# WiFiSensor.net
KiCad netlist of a schematic drawn in EAGLE
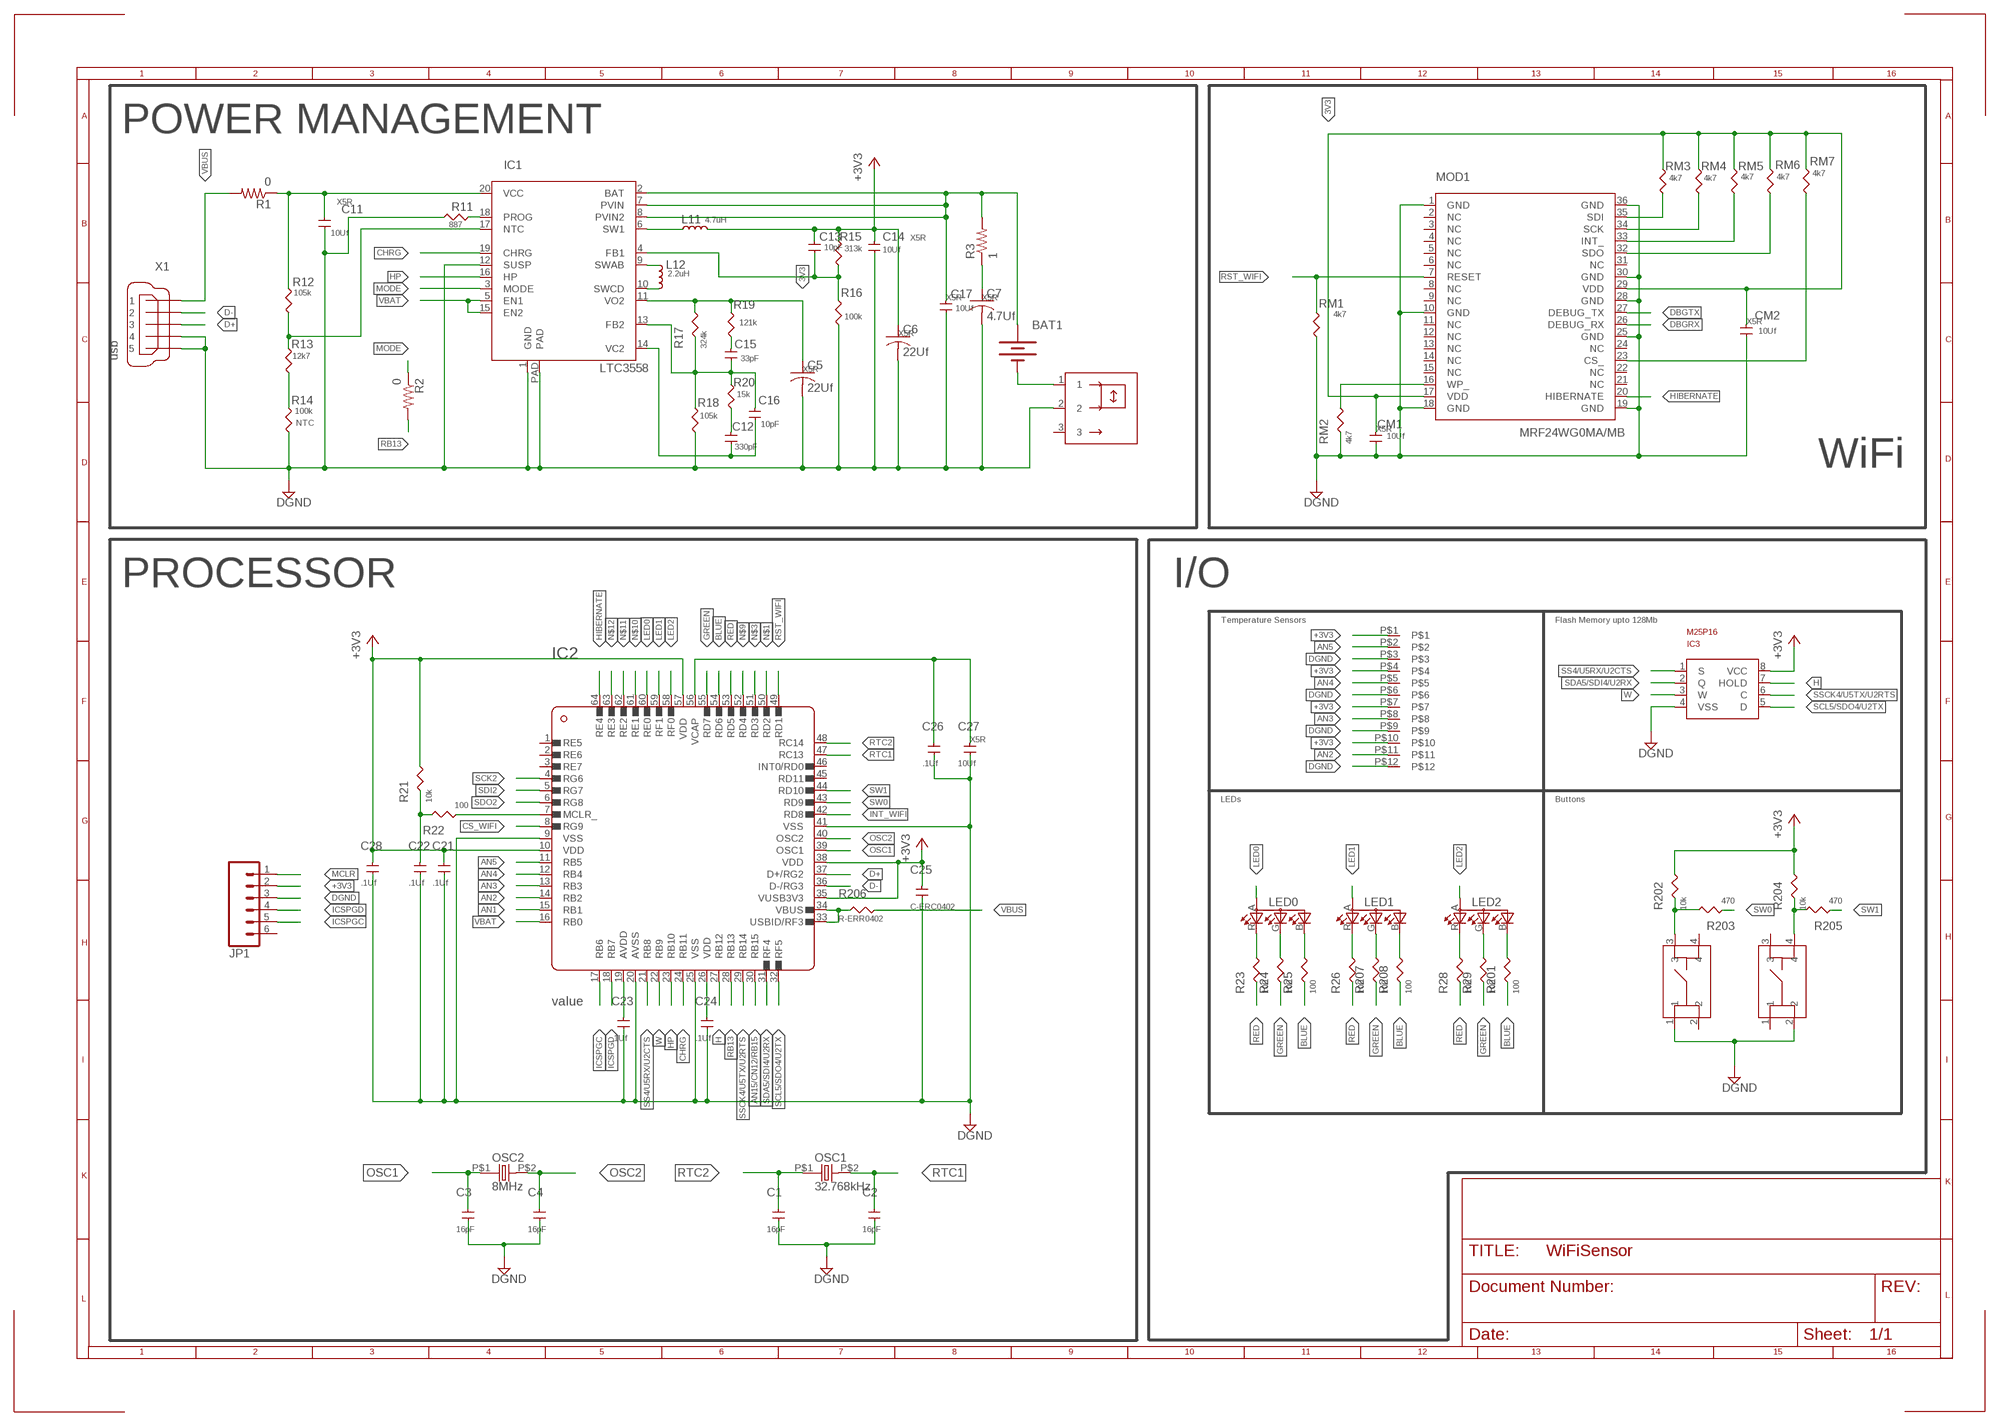
[diagram p0: schematic, sheet 1]

(export (version "E")
  (design (tool "Eeschema 10.0.6"))
  (components
    (comp (ref "BAT1")
      (value "BATTERY245PTH")
      (footprint "eagle-import:BATTCON_245MM_PTH")
      (libsource (lib "eagle-import") (part "BATTERY245PTH"))
    )
    (comp (ref "C1")
      (value "16pF")
      (footprint "eagle-import:C0402")
      (libsource (lib "eagle-import") (part "C-ERC0402"))
    )
    (comp (ref "C2")
      (value "16pF")
      (footprint "eagle-import:C0402")
      (libsource (lib "eagle-import") (part "C-ERC0402"))
    )
    (comp (ref "C3")
      (value "16pF")
      (footprint "eagle-import:C0402")
      (libsource (lib "eagle-import") (part "C-ERC0402"))
    )
    (comp (ref "C4")
      (value "16pF")
      (footprint "eagle-import:C0402")
      (libsource (lib "eagle-import") (part "C-ERC0402"))
    )
    (comp (ref "C5")
      (value "22Uf")
      (footprint "eagle-import:C0805")
      (fields (field (name "TEMPCHAR") "X5R"))
      (libsource (lib "eagle-import") (part "C-USC0805"))
    )
    (comp (ref "C6")
      (value "22Uf")
      (footprint "eagle-import:C0805")
      (fields (field (name "TEMPCHAR") "X5R"))
      (libsource (lib "eagle-import") (part "C-USC0805"))
    )
    (comp (ref "C7")
      (value "4.7Uf")
      (footprint "eagle-import:C0402")
      (fields (field (name "TEMPCHAR") "X5R"))
      (libsource (lib "eagle-import") (part "C-USC0402"))
    )
    (comp (ref "C11")
      (value "10Uf")
      (footprint "eagle-import:C0805")
      (fields (field (name "TEMPCHAR") "X5R"))
      (libsource (lib "eagle-import") (part "C-ER"))
    )
    (comp (ref "C12")
      (value "330pF")
      (footprint "eagle-import:C0402")
      (libsource (lib "eagle-import") (part "C-ERC0402"))
    )
    (comp (ref "C13")
      (value "10pF")
      (footprint "eagle-import:C0402")
      (libsource (lib "eagle-import") (part "C-ERC0402"))
    )
    (comp (ref "C14")
      (value "10Uf")
      (footprint "eagle-import:C0805")
      (fields (field (name "TEMPCHAR") "X5R"))
      (libsource (lib "eagle-import") (part "C-ER"))
    )
    (comp (ref "C15")
      (value "33pF")
      (footprint "eagle-import:C0402")
      (libsource (lib "eagle-import") (part "C-ERC0402"))
    )
    (comp (ref "C16")
      (value "10pF")
      (footprint "eagle-import:C0402")
      (libsource (lib "eagle-import") (part "C-ERC0402"))
    )
    (comp (ref "C17")
      (value "10Uf")
      (footprint "eagle-import:C0805")
      (fields (field (name "TEMPCHAR") "X5R"))
      (libsource (lib "eagle-import") (part "C-ER"))
    )
    (comp (ref "C21")
      (value ".1Uf")
      (footprint "eagle-import:C0402")
      (libsource (lib "eagle-import") (part "C-ERC0402"))
    )
    (comp (ref "C22")
      (value ".1Uf")
      (footprint "eagle-import:C0402")
      (libsource (lib "eagle-import") (part "C-ERC0402"))
    )
    (comp (ref "C23")
      (value ".1Uf")
      (footprint "eagle-import:C0402")
      (libsource (lib "eagle-import") (part "C-ERC0402"))
    )
    (comp (ref "C24")
      (value ".1Uf")
      (footprint "eagle-import:C0402")
      (libsource (lib "eagle-import") (part "C-ERC0402"))
    )
    (comp (ref "C25")
      (value "C-ERC0402")
      (footprint "eagle-import:C0402")
      (libsource (lib "eagle-import") (part "C-ERC0402"))
    )
    (comp (ref "C26")
      (value ".1Uf")
      (footprint "eagle-import:C0402")
      (libsource (lib "eagle-import") (part "C-ERC0402"))
    )
    (comp (ref "C27")
      (value "10Uf")
      (footprint "eagle-import:C0805")
      (fields (field (name "TEMPCHAR") "X5R"))
      (libsource (lib "eagle-import") (part "C-ER"))
    )
    (comp (ref "C28")
      (value ".1Uf")
      (footprint "eagle-import:C0402")
      (libsource (lib "eagle-import") (part "C-ERC0402"))
    )
    (comp (ref "CM1")
      (value "10Uf")
      (footprint "eagle-import:C0805")
      (fields (field (name "TEMPCHAR") "X5R"))
      (libsource (lib "eagle-import") (part "C-ER"))
    )
    (comp (ref "CM2")
      (value "10Uf")
      (footprint "eagle-import:C0805")
      (fields (field (name "TEMPCHAR") "X5R"))
      (libsource (lib "eagle-import") (part "C-ER"))
    )
    (comp (ref "IC1")
      (value "LTC3558")
      (footprint "eagle-import:QFN20")
      (libsource (lib "eagle-import") (part "LTC3558"))
    )
    (comp (ref "IC2")
      (value "PICMX32695F512H")
      (footprint "eagle-import:TQFP64")
      (libsource (lib "eagle-import") (part "PICMX32695F512H"))
    )
    (comp (ref "IC3")
      (value "M25P16")
      (footprint "eagle-import:VDFPN8")
      (libsource (lib "eagle-import") (part "M25P16"))
    )
    (comp (ref "JP1")
      (value "M06LOCK")
      (footprint "eagle-import:1X06_LOCK")
      (libsource (lib "eagle-import") (part "M06LOCK"))
    )
    (comp (ref "L11")
      (value "4.7uH")
      (footprint "eagle-import:L3010")
      (libsource (lib "eagle-import") (part "L-ER"))
    )
    (comp (ref "L12")
      (value "2.2uH")
      (footprint "eagle-import:L3010")
      (libsource (lib "eagle-import") (part "L-ER"))
    )
    (comp (ref "LED0")
      (value "1X1RGB")
      (footprint "eagle-import:1X1")
      (libsource (lib "eagle-import") (part "1X1RGB"))
    )
    (comp (ref "LED1")
      (value "1X1RGB")
      (footprint "eagle-import:1X1")
      (libsource (lib "eagle-import") (part "1X1RGB"))
    )
    (comp (ref "LED2")
      (value "1X1RGB")
      (footprint "eagle-import:1X1")
      (libsource (lib "eagle-import") (part "1X1RGB"))
    )
    (comp (ref "MOD1")
      (value "MRF24WG0MA/MB")
      (footprint "eagle-import:MRF24")
      (libsource (lib "eagle-import") (part "MRF24WG0MA/MB"))
    )
    (comp (ref "OSC1")
      (value "32.768kHz")
      (footprint "eagle-import:ECX39")
      (fields (field (name "DIGIPART") "XC1658CT-ND"))
      (libsource (lib "eagle-import") (part "ECX32"))
    )
    (comp (ref "OSC2")
      (value "8MHz")
      (footprint "eagle-import:CX532")
      (fields (field (name "DIGIPART") "XC1658CT-ND"))
      (libsource (lib "eagle-import") (part "CX532"))
    )
    (comp (ref "R1")
      (value "0")
      (footprint "eagle-import:R1206")
      (libsource (lib "eagle-import") (part "R-US_R1206"))
    )
    (comp (ref "R2")
      (value "0")
      (footprint "eagle-import:R1206")
      (libsource (lib "eagle-import") (part "R-US_R1206"))
    )
    (comp (ref "R3")
      (value "1")
      (footprint "eagle-import:R0402")
      (libsource (lib "eagle-import") (part "R-US_R0402"))
    )
    (comp (ref "R11")
      (value "887")
      (footprint "eagle-import:R0402")
      (libsource (lib "eagle-import") (part "R-ERR0402"))
    )
    (comp (ref "R12")
      (value "105k")
      (footprint "eagle-import:R0402")
      (libsource (lib "eagle-import") (part "R-ERR0402"))
    )
    (comp (ref "R13")
      (value "12k7")
      (footprint "eagle-import:R0402")
      (libsource (lib "eagle-import") (part "R-ERR0402"))
    )
    (comp (ref "R14")
      (value "100k")
      (footprint "eagle-import:R0402")
      (fields (field (name "NTC") "NTC"))
      (libsource (lib "eagle-import") (part "R-ERR0402"))
    )
    (comp (ref "R15")
      (value "313k")
      (footprint "eagle-import:R0402")
      (libsource (lib "eagle-import") (part "R-ERR0402"))
    )
    (comp (ref "R16")
      (value "100k")
      (footprint "eagle-import:R0402")
      (libsource (lib "eagle-import") (part "R-ERR0402"))
    )
    (comp (ref "R17")
      (value "324k")
      (footprint "eagle-import:R0402")
      (libsource (lib "eagle-import") (part "R-ERR0402"))
    )
    (comp (ref "R18")
      (value "105k")
      (footprint "eagle-import:R0402")
      (libsource (lib "eagle-import") (part "R-ERR0402"))
    )
    (comp (ref "R19")
      (value "121k")
      (footprint "eagle-import:R0402")
      (libsource (lib "eagle-import") (part "R-ERR0402"))
    )
    (comp (ref "R20")
      (value "15k")
      (footprint "eagle-import:R0402")
      (libsource (lib "eagle-import") (part "R-ERR0402"))
    )
    (comp (ref "R21")
      (value "10k")
      (footprint "eagle-import:R0402")
      (libsource (lib "eagle-import") (part "R-ERR0402"))
    )
    (comp (ref "R22")
      (value "100")
      (footprint "eagle-import:R0402")
      (libsource (lib "eagle-import") (part "R-ERR0402"))
    )
    (comp (ref "R23")
      (value "100")
      (footprint "eagle-import:R0402")
      (libsource (lib "eagle-import") (part "R-ERR0402"))
    )
    (comp (ref "R24")
      (value "100")
      (footprint "eagle-import:R0402")
      (libsource (lib "eagle-import") (part "R-ERR0402"))
    )
    (comp (ref "R25")
      (value "100")
      (footprint "eagle-import:R0402")
      (libsource (lib "eagle-import") (part "R-ERR0402"))
    )
    (comp (ref "R26")
      (value "100")
      (footprint "eagle-import:R0402")
      (libsource (lib "eagle-import") (part "R-ERR0402"))
    )
    (comp (ref "R28")
      (value "100")
      (footprint "eagle-import:R0402")
      (libsource (lib "eagle-import") (part "R-ERR0402"))
    )
    (comp (ref "R29")
      (value "100")
      (footprint "eagle-import:R0402")
      (libsource (lib "eagle-import") (part "R-ERR0402"))
    )
    (comp (ref "R201")
      (value "100")
      (footprint "eagle-import:R0402")
      (libsource (lib "eagle-import") (part "R-ERR0402"))
    )
    (comp (ref "R202")
      (value "10k")
      (footprint "eagle-import:R0402")
      (libsource (lib "eagle-import") (part "R-ERR0402"))
    )
    (comp (ref "R203")
      (value "470")
      (footprint "eagle-import:R0402")
      (libsource (lib "eagle-import") (part "R-ERR0402"))
    )
    (comp (ref "R204")
      (value "10k")
      (footprint "eagle-import:R0402")
      (libsource (lib "eagle-import") (part "R-ERR0402"))
    )
    (comp (ref "R205")
      (value "470")
      (footprint "eagle-import:R0402")
      (libsource (lib "eagle-import") (part "R-ERR0402"))
    )
    (comp (ref "R206")
      (value "R-ERR0402")
      (footprint "eagle-import:R0402")
      (libsource (lib "eagle-import") (part "R-ERR0402"))
    )
    (comp (ref "R207")
      (value "100")
      (footprint "eagle-import:R0402")
      (libsource (lib "eagle-import") (part "R-ERR0402"))
    )
    (comp (ref "R208")
      (value "100")
      (footprint "eagle-import:R0402")
      (libsource (lib "eagle-import") (part "R-ERR0402"))
    )
    (comp (ref "RM1")
      (value "4k7")
      (footprint "eagle-import:R0402")
      (libsource (lib "eagle-import") (part "R-ERR0402"))
    )
    (comp (ref "RM2")
      (value "4k7")
      (footprint "eagle-import:R0402")
      (libsource (lib "eagle-import") (part "R-ERR0402"))
    )
    (comp (ref "RM3")
      (value "4k7")
      (footprint "eagle-import:R0402")
      (libsource (lib "eagle-import") (part "R-ERR0402"))
    )
    (comp (ref "RM4")
      (value "4k7")
      (footprint "eagle-import:R0402")
      (libsource (lib "eagle-import") (part "R-ERR0402"))
    )
    (comp (ref "RM5")
      (value "4k7")
      (footprint "eagle-import:R0402")
      (libsource (lib "eagle-import") (part "R-ERR0402"))
    )
    (comp (ref "RM6")
      (value "4k7")
      (footprint "eagle-import:R0402")
      (libsource (lib "eagle-import") (part "R-ERR0402"))
    )
    (comp (ref "RM7")
      (value "4k7")
      (footprint "eagle-import:R0402")
      (libsource (lib "eagle-import") (part "R-ERR0402"))
    )
    (comp (ref "SENSORS")
      (value "12_127")
      (footprint "eagle-import:12-127")
      (libsource (lib "eagle-import") (part "12_127"))
    )
    (comp (ref "U$1")
      (value "C&K_JS")
      (footprint "eagle-import:SAQN")
      (libsource (lib "eagle-import") (part "C&K_JS"))
    )
    (comp (ref "U$2")
      (value "ADTS")
      (footprint "eagle-import:4X5")
      (libsource (lib "eagle-import") (part "ADTS"))
    )
    (comp (ref "U$3")
      (value "ADTS")
      (footprint "eagle-import:4X5")
      (libsource (lib "eagle-import") (part "ADTS"))
    )
    (comp (ref "X1")
      (value "usb")
      (footprint "eagle-import:UX60A-MB-5ST")
      (libsource (lib "eagle-import") (part "MINI-USB-UX60A-MB-5ST"))
    )
  )
  (nets
    (net (code "1") (name "+3V3") (class "Default")
      (node (ref "C13") (pin "2") (pinfunction "P$2_2") (pintype "bidirectional"))
      (node (ref "C14") (pin "2") (pinfunction "P$2_2") (pintype "bidirectional"))
      (node (ref "C21") (pin "2") (pinfunction "P$2_2") (pintype "bidirectional"))
      (node (ref "C23") (pin "2") (pinfunction "P$2_2") (pintype "bidirectional"))
      (node (ref "C24") (pin "2") (pinfunction "P$2_2") (pintype "bidirectional"))
      (node (ref "C25") (pin "2") (pinfunction "P$2_2") (pintype "bidirectional"))
      (node (ref "C28") (pin "2") (pinfunction "P$2_2") (pintype "bidirectional"))
      (node (ref "C6") (pin "1") (pinfunction "1_1") (pintype "passive"))
      (node (ref "IC2") (pin "10") (pinfunction "VDD_10") (pintype "bidirectional"))
      (node (ref "IC2") (pin "19") (pinfunction "AVDD_19") (pintype "bidirectional"))
      (node (ref "IC2") (pin "26") (pinfunction "VDD_26") (pintype "bidirectional"))
      (node (ref "IC2") (pin "35") (pinfunction "VUSB3V3_35") (pintype "bidirectional"))
      (node (ref "IC2") (pin "38") (pinfunction "VDD_38") (pintype "bidirectional"))
      (node (ref "IC2") (pin "57") (pinfunction "VDD_57") (pintype "bidirectional"))
      (node (ref "IC3") (pin "8") (pinfunction "VCC_8") (pintype "bidirectional"))
      (node (ref "JP1") (pin "2") (pinfunction "2_2") (pintype "passive"))
      (node (ref "L11") (pin "P$2") (pinfunction "P$2_P$2") (pintype "bidirectional"))
      (node (ref "R15") (pin "2") (pinfunction "P$2_2") (pintype "bidirectional"))
      (node (ref "R202") (pin "2") (pinfunction "P$2_2") (pintype "bidirectional"))
      (node (ref "R204") (pin "2") (pinfunction "P$2_2") (pintype "bidirectional"))
      (node (ref "R21") (pin "2") (pinfunction "P$2_2") (pintype "bidirectional"))
      (node (ref "SENSORS") (pin "P$1") (pinfunction "P$1_P$1") (pintype "bidirectional"))
      (node (ref "SENSORS") (pin "P$10") (pinfunction "P$10_P$10") (pintype "bidirectional"))
      (node (ref "SENSORS") (pin "P$4") (pinfunction "P$4_P$4") (pintype "bidirectional"))
      (node (ref "SENSORS") (pin "P$7") (pinfunction "P$7_P$7") (pintype "bidirectional"))
    )
    (net (code "2") (name "3V3") (class "Default")
      (node (ref "C5") (pin "1") (pinfunction "1_1") (pintype "passive"))
      (node (ref "CM1") (pin "2") (pinfunction "P$2_2") (pintype "bidirectional"))
      (node (ref "CM2") (pin "2") (pinfunction "P$2_2") (pintype "bidirectional"))
      (node (ref "IC1") (pin "11") (pinfunction "VO2_11") (pintype "bidirectional"))
      (node (ref "MOD1") (pin "17") (pinfunction "VDD_17") (pintype "bidirectional"))
      (node (ref "MOD1") (pin "29") (pinfunction "VDD_29") (pintype "bidirectional"))
      (node (ref "R17") (pin "2") (pinfunction "P$2_2") (pintype "bidirectional"))
      (node (ref "R19") (pin "2") (pinfunction "P$2_2") (pintype "bidirectional"))
      (node (ref "RM3") (pin "2") (pinfunction "P$2_2") (pintype "bidirectional"))
      (node (ref "RM4") (pin "2") (pinfunction "P$2_2") (pintype "bidirectional"))
      (node (ref "RM5") (pin "2") (pinfunction "P$2_2") (pintype "bidirectional"))
      (node (ref "RM6") (pin "2") (pinfunction "P$2_2") (pintype "bidirectional"))
      (node (ref "RM7") (pin "2") (pinfunction "P$2_2") (pintype "bidirectional"))
    )
    (net (code "3") (name "AN1") (class "Default")
      (node (ref "IC2") (pin "15") (pinfunction "RB1_15") (pintype "bidirectional"))
    )
    (net (code "4") (name "AN2") (class "Default")
      (node (ref "IC2") (pin "14") (pinfunction "RB2_14") (pintype "bidirectional"))
      (node (ref "SENSORS") (pin "P$11") (pinfunction "P$11_P$11") (pintype "bidirectional"))
    )
    (net (code "5") (name "AN3") (class "Default")
      (node (ref "IC2") (pin "13") (pinfunction "RB3_13") (pintype "bidirectional"))
      (node (ref "SENSORS") (pin "P$8") (pinfunction "P$8_P$8") (pintype "bidirectional"))
    )
    (net (code "6") (name "AN4") (class "Default")
      (node (ref "IC2") (pin "12") (pinfunction "RB4_12") (pintype "bidirectional"))
      (node (ref "SENSORS") (pin "P$5") (pinfunction "P$5_P$5") (pintype "bidirectional"))
    )
    (net (code "7") (name "AN5") (class "Default")
      (node (ref "IC2") (pin "11") (pinfunction "RB5_11") (pintype "bidirectional"))
      (node (ref "SENSORS") (pin "P$2") (pinfunction "P$2_P$2") (pintype "bidirectional"))
    )
    (net (code "8") (name "AN15{slash}CN12{slash}RB15") (class "Default")
      (node (ref "IC2") (pin "30") (pinfunction "RB15_30") (pintype "bidirectional"))
    )
    (net (code "9") (name "BLUE") (class "Default")
      (node (ref "IC2") (pin "54") (pinfunction "RD6_54") (pintype "bidirectional"))
      (node (ref "R201") (pin "1") (pinfunction "P$1_1") (pintype "bidirectional"))
      (node (ref "R208") (pin "1") (pinfunction "P$1_1") (pintype "bidirectional"))
      (node (ref "R25") (pin "1") (pinfunction "P$1_1") (pintype "bidirectional"))
    )
    (net (code "10") (name "CHRG") (class "Default")
      (node (ref "IC1") (pin "19") (pinfunction "CHRG_19") (pintype "bidirectional"))
      (node (ref "IC2") (pin "24") (pinfunction "RB11_24") (pintype "bidirectional"))
    )
    (net (code "11") (name "CS_WIFI") (class "Default")
      (node (ref "IC2") (pin "8") (pinfunction "RG9_8") (pintype "bidirectional"))
      (node (ref "MOD1") (pin "23") (pinfunction "CS__23") (pintype "bidirectional"))
      (node (ref "RM7") (pin "1") (pinfunction "P$1_1") (pintype "bidirectional"))
    )
    (net (code "12") (name "D+") (class "Default")
      (node (ref "IC2") (pin "37") (pinfunction "D+/RG2_37") (pintype "bidirectional"))
      (node (ref "X1") (pin "3") (pinfunction "3_3") (pintype "input"))
    )
    (net (code "13") (name "D-") (class "Default")
      (node (ref "IC2") (pin "36") (pinfunction "D-/RG3_36") (pintype "bidirectional"))
      (node (ref "X1") (pin "2") (pinfunction "2_2") (pintype "input"))
    )
    (net (code "14") (name "DBGRX") (class "Default")
      (node (ref "MOD1") (pin "26") (pinfunction "DEBUG_RX_26") (pintype "bidirectional"))
    )
    (net (code "15") (name "DBGTX") (class "Default")
      (node (ref "MOD1") (pin "27") (pinfunction "DEBUG_TX_27") (pintype "bidirectional"))
    )
    (net (code "16") (name "DGND") (class "Default")
      (node (ref "C1") (pin "1") (pinfunction "P$1_1") (pintype "bidirectional"))
      (node (ref "C11") (pin "1") (pinfunction "P$1_1") (pintype "bidirectional"))
      (node (ref "C14") (pin "1") (pinfunction "P$1_1") (pintype "bidirectional"))
      (node (ref "C17") (pin "1") (pinfunction "P$1_1") (pintype "bidirectional"))
      (node (ref "C2") (pin "1") (pinfunction "P$1_1") (pintype "bidirectional"))
      (node (ref "C21") (pin "1") (pinfunction "P$1_1") (pintype "bidirectional"))
      (node (ref "C22") (pin "1") (pinfunction "P$1_1") (pintype "bidirectional"))
      (node (ref "C23") (pin "1") (pinfunction "P$1_1") (pintype "bidirectional"))
      (node (ref "C24") (pin "1") (pinfunction "P$1_1") (pintype "bidirectional"))
      (node (ref "C25") (pin "1") (pinfunction "P$1_1") (pintype "bidirectional"))
      (node (ref "C26") (pin "1") (pinfunction "P$1_1") (pintype "bidirectional"))
      (node (ref "C27") (pin "1") (pinfunction "P$1_1") (pintype "bidirectional"))
      (node (ref "C28") (pin "1") (pinfunction "P$1_1") (pintype "bidirectional"))
      (node (ref "C3") (pin "1") (pinfunction "P$1_1") (pintype "bidirectional"))
      (node (ref "C4") (pin "1") (pinfunction "P$1_1") (pintype "bidirectional"))
      (node (ref "C5") (pin "2") (pinfunction "2_2") (pintype "passive"))
      (node (ref "C6") (pin "2") (pinfunction "2_2") (pintype "passive"))
      (node (ref "C7") (pin "2") (pinfunction "2_2") (pintype "passive"))
      (node (ref "CM1") (pin "1") (pinfunction "P$1_1") (pintype "bidirectional"))
      (node (ref "CM2") (pin "1") (pinfunction "P$1_1") (pintype "bidirectional"))
      (node (ref "IC1") (pin "1") (pinfunction "GND_1") (pintype "bidirectional"))
      (node (ref "IC1") (pin "12") (pinfunction "SUSP_12") (pintype "bidirectional"))
      (node (ref "IC1") (pin "PAD") (pinfunction "PAD_PAD") (pintype "bidirectional"))
      (node (ref "IC2") (pin "20") (pinfunction "AVSS_20") (pintype "bidirectional"))
      (node (ref "IC2") (pin "25") (pinfunction "VSS_25") (pintype "bidirectional"))
      (node (ref "IC2") (pin "41") (pinfunction "VSS_41") (pintype "bidirectional"))
      (node (ref "IC2") (pin "9") (pinfunction "VSS_9") (pintype "bidirectional"))
      (node (ref "IC3") (pin "4") (pinfunction "VSS_4") (pintype "bidirectional"))
      (node (ref "JP1") (pin "3") (pinfunction "3_3") (pintype "passive"))
      (node (ref "MOD1") (pin "1") (pinfunction "GND_1") (pintype "bidirectional"))
      (node (ref "MOD1") (pin "10") (pinfunction "GND_10") (pintype "bidirectional"))
      (node (ref "MOD1") (pin "18") (pinfunction "GND_18") (pintype "bidirectional"))
      (node (ref "MOD1") (pin "19") (pinfunction "GND_19") (pintype "bidirectional"))
      (node (ref "MOD1") (pin "25") (pinfunction "GND_25") (pintype "bidirectional"))
      (node (ref "MOD1") (pin "28") (pinfunction "GND_28") (pintype "bidirectional"))
      (node (ref "MOD1") (pin "30") (pinfunction "GND_30") (pintype "bidirectional"))
      (node (ref "MOD1") (pin "36") (pinfunction "GND_36") (pintype "bidirectional"))
      (node (ref "R11") (pin "2") (pinfunction "P$2_2") (pintype "bidirectional"))
      (node (ref "R14") (pin "1") (pinfunction "P$1_1") (pintype "bidirectional"))
      (node (ref "R16") (pin "1") (pinfunction "P$1_1") (pintype "bidirectional"))
      (node (ref "R18") (pin "1") (pinfunction "P$1_1") (pintype "bidirectional"))
      (node (ref "RM1") (pin "1") (pinfunction "P$1_1") (pintype "bidirectional"))
      (node (ref "RM2") (pin "1") (pinfunction "P$1_1") (pintype "bidirectional"))
      (node (ref "SENSORS") (pin "P$12") (pinfunction "P$12_P$12") (pintype "bidirectional"))
      (node (ref "SENSORS") (pin "P$3") (pinfunction "P$3_P$3") (pintype "bidirectional"))
      (node (ref "SENSORS") (pin "P$6") (pinfunction "P$6_P$6") (pintype "bidirectional"))
      (node (ref "SENSORS") (pin "P$9") (pinfunction "P$9_P$9") (pintype "bidirectional"))
      (node (ref "U$1") (pin "2") (pinfunction "2_2") (pintype "bidirectional"))
      (node (ref "U$2") (pin "2") (pinfunction "2_2") (pintype "bidirectional"))
      (node (ref "U$3") (pin "1") (pinfunction "1_1") (pintype "bidirectional"))
      (node (ref "X1") (pin "4") (pinfunction "4_4") (pintype "input"))
      (node (ref "X1") (pin "5") (pinfunction "5_5") (pintype "input"))
    )
    (net (code "17") (name "GREEN") (class "Default")
      (node (ref "IC2") (pin "55") (pinfunction "RD7_55") (pintype "bidirectional"))
      (node (ref "R207") (pin "1") (pinfunction "P$1_1") (pintype "bidirectional"))
      (node (ref "R24") (pin "1") (pinfunction "P$1_1") (pintype "bidirectional"))
      (node (ref "R29") (pin "1") (pinfunction "P$1_1") (pintype "bidirectional"))
    )
    (net (code "18") (name "H") (class "Default")
      (node (ref "IC2") (pin "27") (pinfunction "RB12_27") (pintype "bidirectional"))
      (node (ref "IC3") (pin "7") (pinfunction "HOLD_7") (pintype "bidirectional"))
    )
    (net (code "19") (name "HIBERNATE") (class "Default")
      (node (ref "IC2") (pin "64") (pinfunction "RE4_64") (pintype "bidirectional"))
      (node (ref "MOD1") (pin "20") (pinfunction "HIBERNATE_20") (pintype "bidirectional"))
    )
    (net (code "20") (name "HP") (class "Default")
      (node (ref "IC1") (pin "16") (pinfunction "HP_16") (pintype "bidirectional"))
      (node (ref "IC2") (pin "23") (pinfunction "RB10_23") (pintype "bidirectional"))
    )
    (net (code "21") (name "ICSPGC") (class "Default")
      (node (ref "IC2") (pin "17") (pinfunction "RB6_17") (pintype "bidirectional"))
      (node (ref "JP1") (pin "5") (pinfunction "5_5") (pintype "passive"))
    )
    (net (code "22") (name "ICSPGD") (class "Default")
      (node (ref "IC2") (pin "18") (pinfunction "RB7_18") (pintype "bidirectional"))
      (node (ref "JP1") (pin "4") (pinfunction "4_4") (pintype "passive"))
    )
    (net (code "23") (name "INT_WIFI") (class "Default")
      (node (ref "IC2") (pin "42") (pinfunction "RD8_42") (pintype "bidirectional"))
      (node (ref "MOD1") (pin "33") (pinfunction "INT__33") (pintype "bidirectional"))
      (node (ref "RM5") (pin "1") (pinfunction "P$1_1") (pintype "bidirectional"))
    )
    (net (code "24") (name "LED0") (class "Default")
      (node (ref "IC2") (pin "60") (pinfunction "RE0_60") (pintype "bidirectional"))
      (node (ref "LED0") (pin "A") (pinfunction "A2_A") (pintype "passive"))
    )
    (net (code "25") (name "LED1") (class "Default")
      (node (ref "IC2") (pin "59") (pinfunction "RF1_59") (pintype "bidirectional"))
      (node (ref "LED1") (pin "A") (pinfunction "A2_A") (pintype "passive"))
    )
    (net (code "26") (name "LED2") (class "Default")
      (node (ref "IC2") (pin "58") (pinfunction "RF0_58") (pintype "bidirectional"))
      (node (ref "LED2") (pin "A") (pinfunction "A2_A") (pintype "passive"))
    )
    (net (code "27") (name "MCLR") (class "Default")
      (node (ref "C22") (pin "2") (pinfunction "P$2_2") (pintype "bidirectional"))
      (node (ref "JP1") (pin "1") (pinfunction "1_1") (pintype "passive"))
      (node (ref "R21") (pin "1") (pinfunction "P$1_1") (pintype "bidirectional"))
      (node (ref "R22") (pin "2") (pinfunction "P$2_2") (pintype "bidirectional"))
    )
    (net (code "28") (name "MODE") (class "Default")
      (node (ref "IC1") (pin "3") (pinfunction "MODE_3") (pintype "bidirectional"))
      (node (ref "R2") (pin "1") (pinfunction "1_1") (pintype "passive"))
    )
    (net (code "29") (name "N$1") (class "Default")
      (node (ref "IC2") (pin "50") (pinfunction "RD2_50") (pintype "bidirectional"))
    )
    (net (code "30") (name "N$3") (class "Default")
      (node (ref "IC2") (pin "51") (pinfunction "RD3_51") (pintype "bidirectional"))
    )
    (net (code "31") (name "N$9") (class "Default")
      (node (ref "IC2") (pin "52") (pinfunction "RD4_52") (pintype "bidirectional"))
    )
    (net (code "32") (name "N$10") (class "Default")
      (node (ref "IC2") (pin "61") (pinfunction "RE1_61") (pintype "bidirectional"))
    )
    (net (code "33") (name "N$11") (class "Default")
      (node (ref "IC2") (pin "62") (pinfunction "RE2_62") (pintype "bidirectional"))
    )
    (net (code "34") (name "N$12") (class "Default")
      (node (ref "IC2") (pin "63") (pinfunction "RE3_63") (pintype "bidirectional"))
    )
    (net (code "35") (name "Net-(BAT1--)") (class "Default")
      (node (ref "BAT1") (pin "2") (pinfunction "-_2") (pintype "power_in"))
      (node (ref "U$1") (pin "1") (pinfunction "1_1") (pintype "bidirectional"))
    )
    (net (code "36") (name "Net-(C7-Pad1)") (class "Default")
      (node (ref "C7") (pin "1") (pinfunction "1_1") (pintype "passive"))
      (node (ref "R3") (pin "1") (pinfunction "1_1") (pintype "passive"))
    )
    (net (code "37") (name "Net-(C11-P$2)") (class "Default")
      (node (ref "C11") (pin "2") (pinfunction "P$2_2") (pintype "bidirectional"))
      (node (ref "IC1") (pin "20") (pinfunction "VCC_20") (pintype "bidirectional"))
      (node (ref "R1") (pin "1") (pinfunction "1_1") (pintype "passive"))
      (node (ref "R12") (pin "2") (pinfunction "P$2_2") (pintype "bidirectional"))
    )
    (net (code "38") (name "Net-(C12-P$1)") (class "Default")
      (node (ref "C12") (pin "1") (pinfunction "P$1_1") (pintype "bidirectional"))
      (node (ref "C16") (pin "1") (pinfunction "P$1_1") (pintype "bidirectional"))
      (node (ref "IC1") (pin "14") (pinfunction "VC2_14") (pintype "bidirectional"))
    )
    (net (code "39") (name "Net-(C12-P$2)") (class "Default")
      (node (ref "C12") (pin "2") (pinfunction "P$2_2") (pintype "bidirectional"))
      (node (ref "R20") (pin "1") (pinfunction "P$1_1") (pintype "bidirectional"))
    )
    (net (code "40") (name "Net-(C13-P$1)") (class "Default")
      (node (ref "C13") (pin "1") (pinfunction "P$1_1") (pintype "bidirectional"))
      (node (ref "IC1") (pin "4") (pinfunction "FB1_4") (pintype "bidirectional"))
      (node (ref "R15") (pin "1") (pinfunction "P$1_1") (pintype "bidirectional"))
      (node (ref "R16") (pin "2") (pinfunction "P$2_2") (pintype "bidirectional"))
    )
    (net (code "41") (name "Net-(C15-P$1)") (class "Default")
      (node (ref "C15") (pin "1") (pinfunction "P$1_1") (pintype "bidirectional"))
      (node (ref "C16") (pin "2") (pinfunction "P$2_2") (pintype "bidirectional"))
      (node (ref "IC1") (pin "13") (pinfunction "FB2_13") (pintype "bidirectional"))
      (node (ref "R17") (pin "1") (pinfunction "P$1_1") (pintype "bidirectional"))
      (node (ref "R18") (pin "2") (pinfunction "P$2_2") (pintype "bidirectional"))
      (node (ref "R20") (pin "2") (pinfunction "P$2_2") (pintype "bidirectional"))
    )
    (net (code "42") (name "Net-(C15-P$2)") (class "Default")
      (node (ref "C15") (pin "2") (pinfunction "P$2_2") (pintype "bidirectional"))
      (node (ref "R19") (pin "1") (pinfunction "P$1_1") (pintype "bidirectional"))
    )
    (net (code "43") (name "Net-(C26-P$2)") (class "Default")
      (node (ref "C26") (pin "2") (pinfunction "P$2_2") (pintype "bidirectional"))
      (node (ref "C27") (pin "2") (pinfunction "P$2_2") (pintype "bidirectional"))
      (node (ref "IC2") (pin "56") (pinfunction "VCAP_56") (pintype "bidirectional"))
    )
    (net (code "44") (name "Net-(IC1-NTC)") (class "Default")
      (node (ref "IC1") (pin "17") (pinfunction "NTC_17") (pintype "bidirectional"))
      (node (ref "R12") (pin "1") (pinfunction "P$1_1") (pintype "bidirectional"))
      (node (ref "R13") (pin "2") (pinfunction "P$2_2") (pintype "bidirectional"))
    )
    (net (code "45") (name "Net-(IC1-PROG)") (class "Default")
      (node (ref "IC1") (pin "18") (pinfunction "PROG_18") (pintype "bidirectional"))
      (node (ref "R11") (pin "1") (pinfunction "P$1_1") (pintype "bidirectional"))
    )
    (net (code "46") (name "Net-(IC1-SW1)") (class "Default")
      (node (ref "IC1") (pin "6") (pinfunction "SW1_6") (pintype "bidirectional"))
      (node (ref "L11") (pin "P$1") (pinfunction "P$1_P$1") (pintype "bidirectional"))
    )
    (net (code "47") (name "Net-(IC1-SWAB)") (class "Default")
      (node (ref "IC1") (pin "9") (pinfunction "SWAB_9") (pintype "bidirectional"))
      (node (ref "L12") (pin "P$1") (pinfunction "P$1_P$1") (pintype "bidirectional"))
    )
    (net (code "48") (name "Net-(IC1-SWCD)") (class "Default")
      (node (ref "IC1") (pin "10") (pinfunction "SWCD_10") (pintype "bidirectional"))
      (node (ref "L12") (pin "P$2") (pinfunction "P$2_P$2") (pintype "bidirectional"))
    )
    (net (code "49") (name "Net-(IC2-MCLR_)") (class "Default")
      (node (ref "IC2") (pin "7") (pinfunction "MCLR__7") (pintype "bidirectional"))
      (node (ref "R22") (pin "1") (pinfunction "P$1_1") (pintype "bidirectional"))
    )
    (net (code "50") (name "Net-(IC2-USBID{slash}RF3)") (class "Default")
      (node (ref "IC2") (pin "33") (pinfunction "USBID/RF3_33") (pintype "bidirectional"))
      (node (ref "IC2") (pin "34") (pinfunction "VBUS_34") (pintype "bidirectional"))
      (node (ref "R206") (pin "1") (pinfunction "P$1_1") (pintype "bidirectional"))
    )
    (net (code "51") (name "Net-(LED0-CBLUE)") (class "Default")
      (node (ref "LED0") (pin "G") (pinfunction "CBLUE_G") (pintype "passive"))
      (node (ref "R24") (pin "2") (pinfunction "P$2_2") (pintype "bidirectional"))
    )
    (net (code "52") (name "Net-(LED0-CGREEN)") (class "Default")
      (node (ref "LED0") (pin "B") (pinfunction "CGREEN_B") (pintype "passive"))
      (node (ref "R25") (pin "2") (pinfunction "P$2_2") (pintype "bidirectional"))
    )
    (net (code "53") (name "Net-(LED0-CRED)") (class "Default")
      (node (ref "LED0") (pin "R") (pinfunction "CRED_R") (pintype "passive"))
      (node (ref "R23") (pin "2") (pinfunction "P$2_2") (pintype "bidirectional"))
    )
    (net (code "54") (name "Net-(LED1-CBLUE)") (class "Default")
      (node (ref "LED1") (pin "G") (pinfunction "CBLUE_G") (pintype "passive"))
      (node (ref "R207") (pin "2") (pinfunction "P$2_2") (pintype "bidirectional"))
    )
    (net (code "55") (name "Net-(LED1-CGREEN)") (class "Default")
      (node (ref "LED1") (pin "B") (pinfunction "CGREEN_B") (pintype "passive"))
      (node (ref "R208") (pin "2") (pinfunction "P$2_2") (pintype "bidirectional"))
    )
    (net (code "56") (name "Net-(LED1-CRED)") (class "Default")
      (node (ref "LED1") (pin "R") (pinfunction "CRED_R") (pintype "passive"))
      (node (ref "R26") (pin "2") (pinfunction "P$2_2") (pintype "bidirectional"))
    )
    (net (code "57") (name "Net-(LED2-CBLUE)") (class "Default")
      (node (ref "LED2") (pin "G") (pinfunction "CBLUE_G") (pintype "passive"))
      (node (ref "R29") (pin "2") (pinfunction "P$2_2") (pintype "bidirectional"))
    )
    (net (code "58") (name "Net-(LED2-CGREEN)") (class "Default")
      (node (ref "LED2") (pin "B") (pinfunction "CGREEN_B") (pintype "passive"))
      (node (ref "R201") (pin "2") (pinfunction "P$2_2") (pintype "bidirectional"))
    )
    (net (code "59") (name "Net-(LED2-CRED)") (class "Default")
      (node (ref "LED2") (pin "R") (pinfunction "CRED_R") (pintype "passive"))
      (node (ref "R28") (pin "2") (pinfunction "P$2_2") (pintype "bidirectional"))
    )
    (net (code "60") (name "Net-(MOD1-WP_)") (class "Default")
      (node (ref "MOD1") (pin "16") (pinfunction "WP__16") (pintype "bidirectional"))
      (node (ref "RM2") (pin "2") (pinfunction "P$2_2") (pintype "bidirectional"))
    )
    (net (code "61") (name "Net-(R13-P$1)") (class "Default")
      (node (ref "R13") (pin "1") (pinfunction "P$1_1") (pintype "bidirectional"))
      (node (ref "R14") (pin "2") (pinfunction "P$2_2") (pintype "bidirectional"))
    )
    (net (code "62") (name "Net-(R202-P$1)") (class "Default")
      (node (ref "R202") (pin "1") (pinfunction "P$1_1") (pintype "bidirectional"))
      (node (ref "R203") (pin "2") (pinfunction "P$2_2") (pintype "bidirectional"))
      (node (ref "U$3") (pin "3") (pinfunction "3_3") (pintype "bidirectional"))
    )
    (net (code "63") (name "Net-(R204-P$1)") (class "Default")
      (node (ref "R204") (pin "1") (pinfunction "P$1_1") (pintype "bidirectional"))
      (node (ref "R205") (pin "2") (pinfunction "P$2_2") (pintype "bidirectional"))
      (node (ref "U$2") (pin "4") (pinfunction "4_4") (pintype "bidirectional"))
    )
    (net (code "64") (name "OSC1") (class "Default")
      (node (ref "C3") (pin "2") (pinfunction "P$2_2") (pintype "bidirectional"))
      (node (ref "IC2") (pin "39") (pinfunction "OSC1_39") (pintype "bidirectional"))
      (node (ref "OSC2") (pin "P$1") (pinfunction "1_P$1") (pintype "passive"))
    )
    (net (code "65") (name "OSC2") (class "Default")
      (node (ref "C4") (pin "2") (pinfunction "P$2_2") (pintype "bidirectional"))
      (node (ref "IC2") (pin "40") (pinfunction "OSC2_40") (pintype "bidirectional"))
      (node (ref "OSC2") (pin "P$2") (pinfunction "2_P$2") (pintype "passive"))
    )
    (net (code "66") (name "RB13") (class "Default")
      (node (ref "IC2") (pin "28") (pinfunction "RB13_28") (pintype "bidirectional"))
      (node (ref "R2") (pin "2") (pinfunction "2_2") (pintype "passive"))
    )
    (net (code "67") (name "RED") (class "Default")
      (node (ref "IC2") (pin "53") (pinfunction "RD5_53") (pintype "bidirectional"))
      (node (ref "R23") (pin "1") (pinfunction "P$1_1") (pintype "bidirectional"))
      (node (ref "R26") (pin "1") (pinfunction "P$1_1") (pintype "bidirectional"))
      (node (ref "R28") (pin "1") (pinfunction "P$1_1") (pintype "bidirectional"))
    )
    (net (code "68") (name "RST_WIFI") (class "Default")
      (node (ref "IC2") (pin "49") (pinfunction "RD1_49") (pintype "bidirectional"))
      (node (ref "MOD1") (pin "7") (pinfunction "RESET_7") (pintype "bidirectional"))
      (node (ref "RM1") (pin "2") (pinfunction "P$2_2") (pintype "bidirectional"))
    )
    (net (code "69") (name "RTC1") (class "Default")
      (node (ref "C2") (pin "2") (pinfunction "P$2_2") (pintype "bidirectional"))
      (node (ref "IC2") (pin "47") (pinfunction "RC13_47") (pintype "bidirectional"))
      (node (ref "OSC1") (pin "P$2") (pinfunction "2_P$2") (pintype "passive"))
    )
    (net (code "70") (name "RTC2") (class "Default")
      (node (ref "C1") (pin "2") (pinfunction "P$2_2") (pintype "bidirectional"))
      (node (ref "IC2") (pin "48") (pinfunction "RC14_48") (pintype "bidirectional"))
      (node (ref "OSC1") (pin "P$1") (pinfunction "1_P$1") (pintype "passive"))
    )
    (net (code "71") (name "SCK2") (class "Default")
      (node (ref "IC2") (pin "4") (pinfunction "RG6_4") (pintype "bidirectional"))
      (node (ref "MOD1") (pin "34") (pinfunction "SCK_34") (pintype "bidirectional"))
      (node (ref "RM4") (pin "1") (pinfunction "P$1_1") (pintype "bidirectional"))
    )
    (net (code "72") (name "SCL5{slash}SDO4{slash}U2TX") (class "Default")
      (node (ref "IC2") (pin "32") (pinfunction "RF5_32") (pintype "bidirectional"))
      (node (ref "IC3") (pin "5") (pinfunction "D_5") (pintype "bidirectional"))
    )
    (net (code "73") (name "SDA5{slash}SDI4{slash}U2RX") (class "Default")
      (node (ref "IC2") (pin "31") (pinfunction "RF4_31") (pintype "bidirectional"))
      (node (ref "IC3") (pin "2") (pinfunction "Q_2") (pintype "bidirectional"))
    )
    (net (code "74") (name "SDI2") (class "Default")
      (node (ref "IC2") (pin "5") (pinfunction "RG7_5") (pintype "bidirectional"))
      (node (ref "MOD1") (pin "32") (pinfunction "SDO_32") (pintype "bidirectional"))
      (node (ref "RM6") (pin "1") (pinfunction "P$1_1") (pintype "bidirectional"))
    )
    (net (code "75") (name "SDO2") (class "Default")
      (node (ref "IC2") (pin "6") (pinfunction "RG8_6") (pintype "bidirectional"))
      (node (ref "MOD1") (pin "35") (pinfunction "SDI_35") (pintype "bidirectional"))
      (node (ref "RM3") (pin "1") (pinfunction "P$1_1") (pintype "bidirectional"))
    )
    (net (code "76") (name "SS4{slash}U5RX{slash}U2CTS") (class "Default")
      (node (ref "IC2") (pin "21") (pinfunction "RB8_21") (pintype "bidirectional"))
      (node (ref "IC3") (pin "1") (pinfunction "S_1") (pintype "bidirectional"))
    )
    (net (code "77") (name "SSCK4{slash}U5TX{slash}U2RTS") (class "Default")
      (node (ref "IC2") (pin "29") (pinfunction "RB14_29") (pintype "bidirectional"))
      (node (ref "IC3") (pin "6") (pinfunction "C_6") (pintype "bidirectional"))
    )
    (net (code "78") (name "SW0") (class "Default")
      (node (ref "IC2") (pin "43") (pinfunction "RD9_43") (pintype "bidirectional"))
      (node (ref "R203") (pin "1") (pinfunction "P$1_1") (pintype "bidirectional"))
    )
    (net (code "79") (name "SW1") (class "Default")
      (node (ref "IC2") (pin "44") (pinfunction "RD10_44") (pintype "bidirectional"))
      (node (ref "R205") (pin "1") (pinfunction "P$1_1") (pintype "bidirectional"))
    )
    (net (code "80") (name "VBAT") (class "Default")
      (node (ref "BAT1") (pin "3") (pinfunction "+_3") (pintype "power_in"))
      (node (ref "C17") (pin "2") (pinfunction "P$2_2") (pintype "bidirectional"))
      (node (ref "IC1") (pin "15") (pinfunction "EN2_15") (pintype "bidirectional"))
      (node (ref "IC1") (pin "2") (pinfunction "BAT_2") (pintype "bidirectional"))
      (node (ref "IC1") (pin "5") (pinfunction "EN1_5") (pintype "bidirectional"))
      (node (ref "IC1") (pin "7") (pinfunction "PVIN_7") (pintype "bidirectional"))
      (node (ref "IC1") (pin "8") (pinfunction "PVIN2_8") (pintype "bidirectional"))
      (node (ref "IC2") (pin "16") (pinfunction "RB0_16") (pintype "bidirectional"))
      (node (ref "R3") (pin "2") (pinfunction "2_2") (pintype "passive"))
    )
    (net (code "81") (name "VBUS") (class "Default")
      (node (ref "R1") (pin "2") (pinfunction "2_2") (pintype "passive"))
      (node (ref "R206") (pin "2") (pinfunction "P$2_2") (pintype "bidirectional"))
      (node (ref "X1") (pin "1") (pinfunction "1_1") (pintype "input"))
    )
    (net (code "82") (name "W") (class "Default")
      (node (ref "IC2") (pin "22") (pinfunction "RB9_22") (pintype "bidirectional"))
      (node (ref "IC3") (pin "3") (pinfunction "W_3") (pintype "bidirectional"))
    )
    (net (code "83") (name "unconnected-(IC2-INT0{slash}RD0-Pad46)") (class "Default")
      (node (ref "IC2") (pin "46") (pinfunction "INT0/RD0_46") (pintype "bidirectional"))
    )
    (net (code "84") (name "unconnected-(IC2-RD11-Pad45)") (class "Default")
      (node (ref "IC2") (pin "45") (pinfunction "RD11_45") (pintype "bidirectional"))
    )
    (net (code "85") (name "unconnected-(IC2-RE5-Pad1)") (class "Default")
      (node (ref "IC2") (pin "1") (pinfunction "RE5_1") (pintype "bidirectional"))
    )
    (net (code "86") (name "unconnected-(IC2-RE6-Pad2)") (class "Default")
      (node (ref "IC2") (pin "2") (pinfunction "RE6_2") (pintype "bidirectional"))
    )
    (net (code "87") (name "unconnected-(IC2-RE7-Pad3)") (class "Default")
      (node (ref "IC2") (pin "3") (pinfunction "RE7_3") (pintype "bidirectional"))
    )
    (net (code "88") (name "unconnected-(JP1-Pad6)") (class "Default")
      (node (ref "JP1") (pin "6") (pinfunction "6_6") (pintype "passive"))
    )
    (net (code "89") (name "unconnected-(MOD1-NC-Pad2)") (class "Default")
      (node (ref "MOD1") (pin "2") (pinfunction "NC_2") (pintype "bidirectional"))
    )
    (net (code "90") (name "unconnected-(MOD1-NC-Pad3)") (class "Default")
      (node (ref "MOD1") (pin "3") (pinfunction "NC_3") (pintype "bidirectional"))
    )
    (net (code "91") (name "unconnected-(MOD1-NC-Pad4)") (class "Default")
      (node (ref "MOD1") (pin "4") (pinfunction "NC_4") (pintype "bidirectional"))
    )
    (net (code "92") (name "unconnected-(MOD1-NC-Pad5)") (class "Default")
      (node (ref "MOD1") (pin "5") (pinfunction "NC_5") (pintype "bidirectional"))
    )
    (net (code "93") (name "unconnected-(MOD1-NC-Pad6)") (class "Default")
      (node (ref "MOD1") (pin "6") (pinfunction "NC_6") (pintype "bidirectional"))
    )
    (net (code "94") (name "unconnected-(MOD1-NC-Pad8)") (class "Default")
      (node (ref "MOD1") (pin "8") (pinfunction "NC_8") (pintype "bidirectional"))
    )
    (net (code "95") (name "unconnected-(MOD1-NC-Pad9)") (class "Default")
      (node (ref "MOD1") (pin "9") (pinfunction "NC_9") (pintype "bidirectional"))
    )
    (net (code "96") (name "unconnected-(MOD1-NC-Pad11)") (class "Default")
      (node (ref "MOD1") (pin "11") (pinfunction "NC_11") (pintype "bidirectional"))
    )
    (net (code "97") (name "unconnected-(MOD1-NC-Pad12)") (class "Default")
      (node (ref "MOD1") (pin "12") (pinfunction "NC_12") (pintype "bidirectional"))
    )
    (net (code "98") (name "unconnected-(MOD1-NC-Pad13)") (class "Default")
      (node (ref "MOD1") (pin "13") (pinfunction "NC_13") (pintype "bidirectional"))
    )
    (net (code "99") (name "unconnected-(MOD1-NC-Pad14)") (class "Default")
      (node (ref "MOD1") (pin "14") (pinfunction "NC_14") (pintype "bidirectional"))
    )
    (net (code "100") (name "unconnected-(MOD1-NC-Pad15)") (class "Default")
      (node (ref "MOD1") (pin "15") (pinfunction "NC_15") (pintype "bidirectional"))
    )
    (net (code "101") (name "unconnected-(MOD1-NC-Pad21)") (class "Default")
      (node (ref "MOD1") (pin "21") (pinfunction "NC_21") (pintype "bidirectional"))
    )
    (net (code "102") (name "unconnected-(MOD1-NC-Pad22)") (class "Default")
      (node (ref "MOD1") (pin "22") (pinfunction "NC_22") (pintype "bidirectional"))
    )
    (net (code "103") (name "unconnected-(MOD1-NC-Pad24)") (class "Default")
      (node (ref "MOD1") (pin "24") (pinfunction "NC_24") (pintype "bidirectional"))
    )
    (net (code "104") (name "unconnected-(MOD1-NC-Pad31)") (class "Default")
      (node (ref "MOD1") (pin "31") (pinfunction "NC_31") (pintype "bidirectional"))
    )
    (net (code "105") (name "unconnected-(U$1-Pad3)") (class "Default")
      (node (ref "U$1") (pin "3") (pinfunction "3_3") (pintype "bidirectional"))
    )
    (net (code "106") (name "unconnected-(U$2-Pad1)") (class "Default")
      (node (ref "U$2") (pin "1") (pinfunction "1_1") (pintype "bidirectional"))
    )
    (net (code "107") (name "unconnected-(U$2-Pad3)") (class "Default")
      (node (ref "U$2") (pin "3") (pinfunction "3_3") (pintype "bidirectional"))
    )
    (net (code "108") (name "unconnected-(U$3-Pad2)") (class "Default")
      (node (ref "U$3") (pin "2") (pinfunction "2_2") (pintype "bidirectional"))
    )
    (net (code "109") (name "unconnected-(U$3-Pad4)") (class "Default")
      (node (ref "U$3") (pin "4") (pinfunction "4_4") (pintype "bidirectional"))
    )
  )
)
